# Mcu.net
KiCad netlist of a schematic drawn in Altium Designer
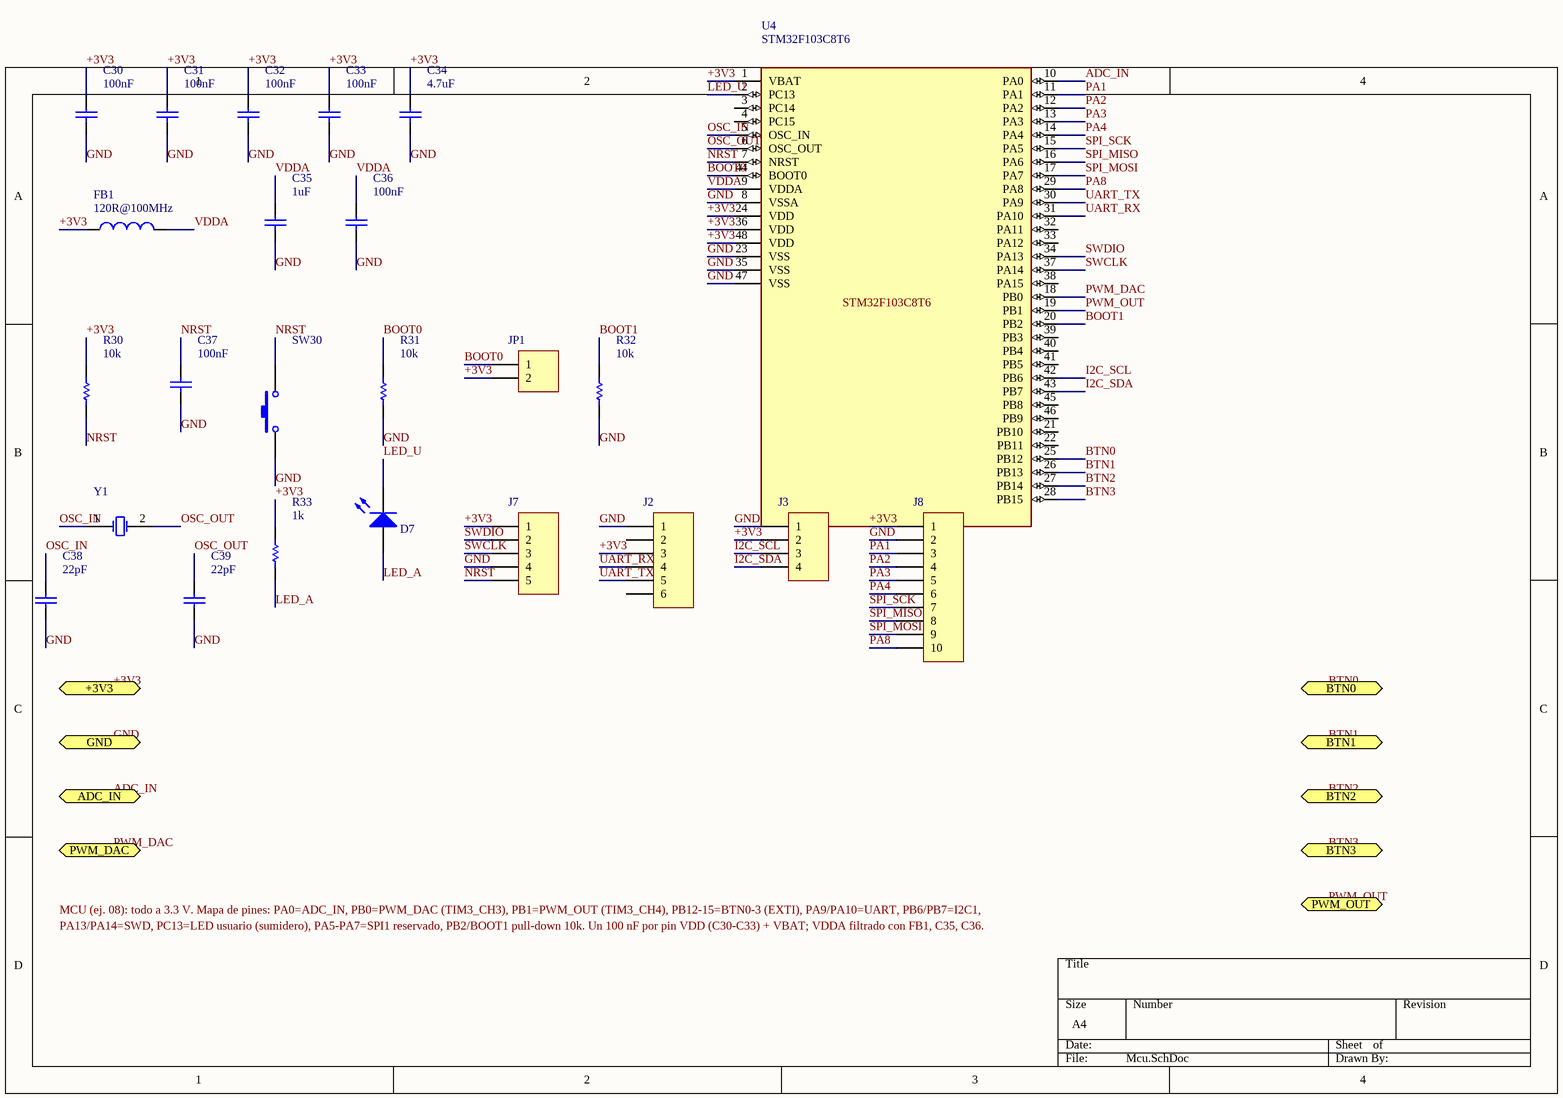
[diagram p0: Mcu.SchDoc]

(export (version "E")
  (design (tool "Eeschema 10.0.6"))
  (components
    (comp (ref "C30")
      (value "100nF")
      (description "Capacitor 100nF")
      (fields
        (field (name "MANUFACTURER") "KEMET")
        (field (name "MANUFACTURER PART NUMBER") "C0603C100nF")
        (field (name "PUBLISHER") "Altium Limited")
      )
      (libsource (lib "Miscellaneous Devices") (part "Cap"))
    )
    (comp (ref "C31")
      (value "100nF")
      (description "Capacitor 100nF")
      (fields
        (field (name "MANUFACTURER") "KEMET")
        (field (name "MANUFACTURER PART NUMBER") "C0603C100nF")
        (field (name "PUBLISHER") "Altium Limited")
      )
      (libsource (lib "Miscellaneous Devices") (part "Cap"))
    )
    (comp (ref "C32")
      (value "100nF")
      (description "Capacitor 100nF")
      (fields
        (field (name "MANUFACTURER") "KEMET")
        (field (name "MANUFACTURER PART NUMBER") "C0603C100nF")
        (field (name "PUBLISHER") "Altium Limited")
      )
      (libsource (lib "Miscellaneous Devices") (part "Cap"))
    )
    (comp (ref "C33")
      (value "100nF")
      (description "Capacitor 100nF")
      (fields
        (field (name "MANUFACTURER") "KEMET")
        (field (name "MANUFACTURER PART NUMBER") "C0603C100nF")
        (field (name "PUBLISHER") "Altium Limited")
      )
      (libsource (lib "Miscellaneous Devices") (part "Cap"))
    )
    (comp (ref "C34")
      (value "4.7uF")
      (description "Capacitor 4.7uF")
      (fields
        (field (name "MANUFACTURER") "KEMET")
        (field (name "MANUFACTURER PART NUMBER") "C0805C4754.7uF")
        (field (name "PUBLISHER") "Altium Limited")
      )
      (libsource (lib "Miscellaneous Devices") (part "Cap"))
    )
    (comp (ref "C35")
      (value "1uF")
      (description "Capacitor 1uF")
      (fields
        (field (name "MANUFACTURER") "KEMET")
        (field (name "MANUFACTURER PART NUMBER") "C0603C1051uF")
        (field (name "PUBLISHER") "Altium Limited")
      )
      (libsource (lib "Miscellaneous Devices") (part "Cap"))
    )
    (comp (ref "C36")
      (value "100nF")
      (description "Capacitor 100nF")
      (fields
        (field (name "MANUFACTURER") "KEMET")
        (field (name "MANUFACTURER PART NUMBER") "C0603C100nF")
        (field (name "PUBLISHER") "Altium Limited")
      )
      (libsource (lib "Miscellaneous Devices") (part "Cap"))
    )
    (comp (ref "C37")
      (value "100nF")
      (description "Capacitor 100nF")
      (fields
        (field (name "MANUFACTURER") "KEMET")
        (field (name "MANUFACTURER PART NUMBER") "C0603C100nF")
        (field (name "PUBLISHER") "Altium Limited")
      )
      (libsource (lib "Miscellaneous Devices") (part "Cap"))
    )
    (comp (ref "C38")
      (value "22pF")
      (description "Capacitor 22pF")
      (fields
        (field (name "MANUFACTURER") "KEMET")
        (field (name "MANUFACTURER PART NUMBER") "C0603C22022pF")
        (field (name "PUBLISHER") "Altium Limited")
      )
      (libsource (lib "Miscellaneous Devices") (part "Cap"))
    )
    (comp (ref "C39")
      (value "22pF")
      (description "Capacitor 22pF")
      (fields
        (field (name "MANUFACTURER") "KEMET")
        (field (name "MANUFACTURER PART NUMBER") "C0603C22022pF")
        (field (name "PUBLISHER") "Altium Limited")
      )
      (libsource (lib "Miscellaneous Devices") (part "Cap"))
    )
    (comp (ref "D7")
      (value "LED1")
      (description "LED de usuario (PC13 sumidero)")
      (fields
        (field (name "MANUFACTURER") "Kingbright")
        (field (name "MANUFACTURER PART NUMBER") "WP7113ID")
        (field (name "PUBLISHER") "Altium Limited")
      )
      (libsource (lib "Miscellaneous Devices") (part "LED1"))
    )
    (comp (ref "FB1")
      (value "120R@100MHz")
      (description "Ferrite bead VDD -> VDDA")
      (fields
        (field (name "MANUFACTURER") "Murata")
        (field (name "MANUFACTURER PART NUMBER") "BLM18PG121SN1D")
        (field (name "PUBLISHER") "Altium Limited")
      )
      (libsource (lib "Miscellaneous Devices") (part "Inductor"))
    )
    (comp (ref "J2")
      (value "Header 6")
      (description "UART FTDI: GND, -, 3V3, RX, TX, -")
      (fields
        (field (name "MANUFACTURER") "Generic")
        (field (name "MANUFACTURER PART NUMBER") "Pin header 1x6 FTDI")
        (field (name "PUBLISHER") "Altium Limited")
      )
      (libsource (lib "Miscellaneous Connectors") (part "Header 6"))
    )
    (comp (ref "J3")
      (value "Header 4")
      (description "I2C: GND, 3V3, SCL, SDA")
      (fields
        (field (name "MANUFACTURER") "Generic")
        (field (name "MANUFACTURER PART NUMBER") "Pin header 1x4")
        (field (name "PUBLISHER") "Altium Limited")
      )
      (libsource (lib "Miscellaneous Connectors") (part "Header 4"))
    )
    (comp (ref "J7")
      (value "Header 5")
      (description "SWD: 3V3, SWDIO, SWCLK, GND, NRST")
      (fields
        (field (name "MANUFACTURER") "Generic")
        (field (name "MANUFACTURER PART NUMBER") "Pin header 1x5")
        (field (name "PUBLISHER") "Altium Limited")
      )
      (libsource (lib "Miscellaneous Connectors") (part "Header 5"))
    )
    (comp (ref "J8")
      (value "Header 10")
      (description "Expansion: 3V3, GND, PA1-PA4, SPI SCK/MISO/MOSI, PA8")
      (fields
        (field (name "MANUFACTURER") "Generic")
        (field (name "MANUFACTURER PART NUMBER") "Pin header 1x10")
        (field (name "PUBLISHER") "Altium Limited")
      )
      (libsource (lib "Miscellaneous Connectors") (part "Header 10"))
    )
    (comp (ref "JP1")
      (value "Header 2")
      (description "Jumper BOOT0: cerrado = bootloader UART")
      (fields
        (field (name "MANUFACTURER") "Generic")
        (field (name "MANUFACTURER PART NUMBER") "Pin header 1x2")
        (field (name "PUBLISHER") "Altium Limited")
      )
      (libsource (lib "Miscellaneous Connectors") (part "Header 2"))
    )
    (comp (ref "R30")
      (value "10k")
      (description "Resistor 10k 0603")
      (fields
        (field (name "MANUFACTURER") "Yageo")
        (field (name "MANUFACTURER PART NUMBER") "RC0603FR-0710K")
        (field (name "PUBLISHER") "Altium Limited")
      )
      (libsource (lib "Miscellaneous Devices") (part "Res1"))
    )
    (comp (ref "R31")
      (value "10k")
      (description "Resistor 10k 0603")
      (fields
        (field (name "MANUFACTURER") "Yageo")
        (field (name "MANUFACTURER PART NUMBER") "RC0603FR-0710K")
        (field (name "PUBLISHER") "Altium Limited")
      )
      (libsource (lib "Miscellaneous Devices") (part "Res1"))
    )
    (comp (ref "R32")
      (value "10k")
      (description "Resistor 10k 0603")
      (fields
        (field (name "MANUFACTURER") "Yageo")
        (field (name "MANUFACTURER PART NUMBER") "RC0603FR-0710K")
        (field (name "PUBLISHER") "Altium Limited")
      )
      (libsource (lib "Miscellaneous Devices") (part "Res1"))
    )
    (comp (ref "R33")
      (value "1k")
      (description "Resistor 1k 0603")
      (fields
        (field (name "MANUFACTURER") "Yageo")
        (field (name "MANUFACTURER PART NUMBER") "RC0603FR-071K")
        (field (name "PUBLISHER") "Altium Limited")
      )
      (libsource (lib "Miscellaneous Devices") (part "Res1"))
    )
    (comp (ref "SW30")
      (value "SW-PB")
      (description "Reset manual")
      (fields
        (field (name "MANUFACTURER") "Generic")
        (field (name "MANUFACTURER PART NUMBER") "Tactile 6x6")
        (field (name "PUBLISHER") "Altium Limited")
      )
      (libsource (lib "Miscellaneous Devices") (part "SW-PB"))
    )
    (comp (ref "U4")
      (value "STM32F103C8T6")
      (footprint "LQFP48_7x7")
      (description "STM32F103C8T6 ARM Cortex-M3 72 MHz LQFP48")
      (fields (field (name "MANUFACTURER") "STMicroelectronics"))
      (libsource (lib "*") (part "STM32F103C8T6"))
    )
    (comp (ref "Y1")
      (value "XTAL")
      (description "Cristal 8 MHz CL=20 pF")
      (fields
        (field (name "MANUFACTURER") "Abracon")
        (field (name "MANUFACTURER PART NUMBER") "ABL-8.000MHZ-B2")
        (field (name "PUBLISHER") "Altium Limited")
      )
      (libsource (lib "Miscellaneous Devices") (part "XTAL"))
    )
  )
  (nets
    (net (code "1") (name "/+3V3") (class "Default")
      (node (ref "C30") (pin "2") (pinfunction "2_2") (pintype "passive"))
      (node (ref "C31") (pin "2") (pinfunction "2_2") (pintype "passive"))
      (node (ref "C32") (pin "2") (pinfunction "2_2") (pintype "passive"))
      (node (ref "C33") (pin "2") (pinfunction "2_2") (pintype "passive"))
      (node (ref "C34") (pin "2") (pinfunction "2_2") (pintype "passive"))
      (node (ref "FB1") (pin "1") (pinfunction "1_1") (pintype "passive"))
      (node (ref "J2") (pin "3") (pinfunction "3_3") (pintype "passive"))
      (node (ref "J3") (pin "2") (pinfunction "2_2") (pintype "passive"))
      (node (ref "J7") (pin "1") (pinfunction "1_1") (pintype "passive"))
      (node (ref "J8") (pin "1") (pinfunction "1_1") (pintype "passive"))
      (node (ref "JP1") (pin "2") (pinfunction "2_2") (pintype "passive"))
      (node (ref "R30") (pin "2") (pinfunction "2_2") (pintype "passive"))
      (node (ref "R33") (pin "2") (pinfunction "2_2") (pintype "passive"))
      (node (ref "U4") (pin "1") (pinfunction "VBAT_1") (pintype "power_in"))
      (node (ref "U4") (pin "24") (pinfunction "VDD_24") (pintype "power_in"))
      (node (ref "U4") (pin "36") (pinfunction "VDD_36") (pintype "power_in"))
      (node (ref "U4") (pin "48") (pinfunction "VDD_48") (pintype "power_in"))
    )
    (net (code "2") (name "/ADC_IN") (class "Default")
      (node (ref "U4") (pin "10") (pinfunction "PA0_10") (pintype "bidirectional"))
    )
    (net (code "3") (name "/BOOT0") (class "Default")
      (node (ref "JP1") (pin "1") (pinfunction "1_1") (pintype "passive"))
      (node (ref "R31") (pin "2") (pinfunction "2_2") (pintype "passive"))
      (node (ref "U4") (pin "44") (pinfunction "BOOT0_44") (pintype "bidirectional"))
    )
    (net (code "4") (name "/BOOT1") (class "Default")
      (node (ref "R32") (pin "2") (pinfunction "2_2") (pintype "passive"))
      (node (ref "U4") (pin "20") (pinfunction "PB2_20") (pintype "bidirectional"))
    )
    (net (code "5") (name "/BTN0") (class "Default")
      (node (ref "U4") (pin "25") (pinfunction "PB12_25") (pintype "bidirectional"))
    )
    (net (code "6") (name "/BTN1") (class "Default")
      (node (ref "U4") (pin "26") (pinfunction "PB13_26") (pintype "bidirectional"))
    )
    (net (code "7") (name "/BTN2") (class "Default")
      (node (ref "U4") (pin "27") (pinfunction "PB14_27") (pintype "bidirectional"))
    )
    (net (code "8") (name "/BTN3") (class "Default")
      (node (ref "U4") (pin "28") (pinfunction "PB15_28") (pintype "bidirectional"))
    )
    (net (code "9") (name "/GND") (class "Default")
      (node (ref "C30") (pin "1") (pinfunction "1_1") (pintype "passive"))
      (node (ref "C31") (pin "1") (pinfunction "1_1") (pintype "passive"))
      (node (ref "C32") (pin "1") (pinfunction "1_1") (pintype "passive"))
      (node (ref "C33") (pin "1") (pinfunction "1_1") (pintype "passive"))
      (node (ref "C34") (pin "1") (pinfunction "1_1") (pintype "passive"))
      (node (ref "C35") (pin "1") (pinfunction "1_1") (pintype "passive"))
      (node (ref "C36") (pin "1") (pinfunction "1_1") (pintype "passive"))
      (node (ref "C37") (pin "1") (pinfunction "1_1") (pintype "passive"))
      (node (ref "C38") (pin "1") (pinfunction "1_1") (pintype "passive"))
      (node (ref "C39") (pin "1") (pinfunction "1_1") (pintype "passive"))
      (node (ref "J2") (pin "1") (pinfunction "1_1") (pintype "passive"))
      (node (ref "J3") (pin "1") (pinfunction "1_1") (pintype "passive"))
      (node (ref "J7") (pin "4") (pinfunction "4_4") (pintype "passive"))
      (node (ref "J8") (pin "2") (pinfunction "2_2") (pintype "passive"))
      (node (ref "R31") (pin "1") (pinfunction "1_1") (pintype "passive"))
      (node (ref "R32") (pin "1") (pinfunction "1_1") (pintype "passive"))
      (node (ref "SW30") (pin "1") (pinfunction "1_1") (pintype "passive"))
      (node (ref "U4") (pin "23") (pinfunction "VSS_23") (pintype "power_in"))
      (node (ref "U4") (pin "35") (pinfunction "VSS_35") (pintype "power_in"))
      (node (ref "U4") (pin "47") (pinfunction "VSS_47") (pintype "power_in"))
      (node (ref "U4") (pin "8") (pinfunction "VSSA_8") (pintype "power_in"))
    )
    (net (code "10") (name "/I2C_SCL") (class "Default")
      (node (ref "J3") (pin "3") (pinfunction "3_3") (pintype "passive"))
      (node (ref "U4") (pin "42") (pinfunction "PB6_42") (pintype "bidirectional"))
    )
    (net (code "11") (name "/I2C_SDA") (class "Default")
      (node (ref "J3") (pin "4") (pinfunction "4_4") (pintype "passive"))
      (node (ref "U4") (pin "43") (pinfunction "PB7_43") (pintype "bidirectional"))
    )
    (net (code "12") (name "/LED_A") (class "Default")
      (node (ref "D7") (pin "1") (pinfunction "A_1") (pintype "passive"))
      (node (ref "R33") (pin "1") (pinfunction "1_1") (pintype "passive"))
    )
    (net (code "13") (name "/LED_U") (class "Default")
      (node (ref "D7") (pin "2") (pinfunction "K_2") (pintype "passive"))
      (node (ref "U4") (pin "2") (pinfunction "PC13_2") (pintype "bidirectional"))
    )
    (net (code "14") (name "/NRST") (class "Default")
      (node (ref "C37") (pin "2") (pinfunction "2_2") (pintype "passive"))
      (node (ref "J7") (pin "5") (pinfunction "5_5") (pintype "passive"))
      (node (ref "R30") (pin "1") (pinfunction "1_1") (pintype "passive"))
      (node (ref "SW30") (pin "2") (pinfunction "2_2") (pintype "passive"))
      (node (ref "U4") (pin "7") (pinfunction "NRST_7") (pintype "bidirectional"))
    )
    (net (code "15") (name "/OSC_IN") (class "Default")
      (node (ref "C38") (pin "2") (pinfunction "2_2") (pintype "passive"))
      (node (ref "U4") (pin "5") (pinfunction "OSC_IN_5") (pintype "bidirectional"))
      (node (ref "Y1") (pin "1") (pinfunction "OSC1_1") (pintype "passive"))
    )
    (net (code "16") (name "/OSC_OUT") (class "Default")
      (node (ref "C39") (pin "2") (pinfunction "2_2") (pintype "passive"))
      (node (ref "U4") (pin "6") (pinfunction "OSC_OUT_6") (pintype "bidirectional"))
      (node (ref "Y1") (pin "2") (pinfunction "OSC2_2") (pintype "passive"))
    )
    (net (code "17") (name "/PA1") (class "Default")
      (node (ref "J8") (pin "3") (pinfunction "3_3") (pintype "passive"))
      (node (ref "U4") (pin "11") (pinfunction "PA1_11") (pintype "bidirectional"))
    )
    (net (code "18") (name "/PA2") (class "Default")
      (node (ref "J8") (pin "4") (pinfunction "4_4") (pintype "passive"))
      (node (ref "U4") (pin "12") (pinfunction "PA2_12") (pintype "bidirectional"))
    )
    (net (code "19") (name "/PA3") (class "Default")
      (node (ref "J8") (pin "5") (pinfunction "5_5") (pintype "passive"))
      (node (ref "U4") (pin "13") (pinfunction "PA3_13") (pintype "bidirectional"))
    )
    (net (code "20") (name "/PA4") (class "Default")
      (node (ref "J8") (pin "6") (pinfunction "6_6") (pintype "passive"))
      (node (ref "U4") (pin "14") (pinfunction "PA4_14") (pintype "bidirectional"))
    )
    (net (code "21") (name "/PA8") (class "Default")
      (node (ref "J8") (pin "10") (pinfunction "10_10") (pintype "passive"))
      (node (ref "U4") (pin "29") (pinfunction "PA8_29") (pintype "bidirectional"))
    )
    (net (code "22") (name "/PWM_DAC") (class "Default")
      (node (ref "U4") (pin "18") (pinfunction "PB0_18") (pintype "bidirectional"))
    )
    (net (code "23") (name "/PWM_OUT") (class "Default")
      (node (ref "U4") (pin "19") (pinfunction "PB1_19") (pintype "bidirectional"))
    )
    (net (code "24") (name "/SPI_MISO") (class "Default")
      (node (ref "J8") (pin "8") (pinfunction "8_8") (pintype "passive"))
      (node (ref "U4") (pin "16") (pinfunction "PA6_16") (pintype "bidirectional"))
    )
    (net (code "25") (name "/SPI_MOSI") (class "Default")
      (node (ref "J8") (pin "9") (pinfunction "9_9") (pintype "passive"))
      (node (ref "U4") (pin "17") (pinfunction "PA7_17") (pintype "bidirectional"))
    )
    (net (code "26") (name "/SPI_SCK") (class "Default")
      (node (ref "J8") (pin "7") (pinfunction "7_7") (pintype "passive"))
      (node (ref "U4") (pin "15") (pinfunction "PA5_15") (pintype "bidirectional"))
    )
    (net (code "27") (name "/SWCLK") (class "Default")
      (node (ref "J7") (pin "3") (pinfunction "3_3") (pintype "passive"))
      (node (ref "U4") (pin "37") (pinfunction "PA14_37") (pintype "bidirectional"))
    )
    (net (code "28") (name "/SWDIO") (class "Default")
      (node (ref "J7") (pin "2") (pinfunction "2_2") (pintype "passive"))
      (node (ref "U4") (pin "34") (pinfunction "PA13_34") (pintype "bidirectional"))
    )
    (net (code "29") (name "/UART_RX") (class "Default")
      (node (ref "J2") (pin "4") (pinfunction "4_4") (pintype "passive"))
      (node (ref "U4") (pin "31") (pinfunction "PA10_31") (pintype "bidirectional"))
    )
    (net (code "30") (name "/UART_TX") (class "Default")
      (node (ref "J2") (pin "5") (pinfunction "5_5") (pintype "passive"))
      (node (ref "U4") (pin "30") (pinfunction "PA9_30") (pintype "bidirectional"))
    )
    (net (code "31") (name "/VDDA") (class "Default")
      (node (ref "C35") (pin "2") (pinfunction "2_2") (pintype "passive"))
      (node (ref "C36") (pin "2") (pinfunction "2_2") (pintype "passive"))
      (node (ref "FB1") (pin "2") (pinfunction "2_2") (pintype "passive"))
      (node (ref "U4") (pin "9") (pinfunction "VDDA_9") (pintype "power_in"))
    )
    (net (code "32") (name "unconnected-(J2-Pad2)") (class "Default")
      (node (ref "J2") (pin "2") (pinfunction "2_2") (pintype "passive"))
    )
    (net (code "33") (name "unconnected-(J2-Pad6)") (class "Default")
      (node (ref "J2") (pin "6") (pinfunction "6_6") (pintype "passive"))
    )
    (net (code "34") (name "unconnected-(U4-PA11-Pad32)") (class "Default")
      (node (ref "U4") (pin "32") (pinfunction "PA11_32") (pintype "bidirectional"))
    )
    (net (code "35") (name "unconnected-(U4-PA12-Pad33)") (class "Default")
      (node (ref "U4") (pin "33") (pinfunction "PA12_33") (pintype "bidirectional"))
    )
    (net (code "36") (name "unconnected-(U4-PA15-Pad38)") (class "Default")
      (node (ref "U4") (pin "38") (pinfunction "PA15_38") (pintype "bidirectional"))
    )
    (net (code "37") (name "unconnected-(U4-PB3-Pad39)") (class "Default")
      (node (ref "U4") (pin "39") (pinfunction "PB3_39") (pintype "bidirectional"))
    )
    (net (code "38") (name "unconnected-(U4-PB4-Pad40)") (class "Default")
      (node (ref "U4") (pin "40") (pinfunction "PB4_40") (pintype "bidirectional"))
    )
    (net (code "39") (name "unconnected-(U4-PB5-Pad41)") (class "Default")
      (node (ref "U4") (pin "41") (pinfunction "PB5_41") (pintype "bidirectional"))
    )
    (net (code "40") (name "unconnected-(U4-PB8-Pad45)") (class "Default")
      (node (ref "U4") (pin "45") (pinfunction "PB8_45") (pintype "bidirectional"))
    )
    (net (code "41") (name "unconnected-(U4-PB9-Pad46)") (class "Default")
      (node (ref "U4") (pin "46") (pinfunction "PB9_46") (pintype "bidirectional"))
    )
    (net (code "42") (name "unconnected-(U4-PB10-Pad21)") (class "Default")
      (node (ref "U4") (pin "21") (pinfunction "PB10_21") (pintype "bidirectional"))
    )
    (net (code "43") (name "unconnected-(U4-PB11-Pad22)") (class "Default")
      (node (ref "U4") (pin "22") (pinfunction "PB11_22") (pintype "bidirectional"))
    )
    (net (code "44") (name "unconnected-(U4-PC14-Pad3)") (class "Default")
      (node (ref "U4") (pin "3") (pinfunction "PC14_3") (pintype "bidirectional"))
    )
    (net (code "45") (name "unconnected-(U4-PC15-Pad4)") (class "Default")
      (node (ref "U4") (pin "4") (pinfunction "PC15_4") (pintype "bidirectional"))
    )
  )
)
